# Raspberry_Pi.net
KiCad netlist of a schematic drawn in EAGLE
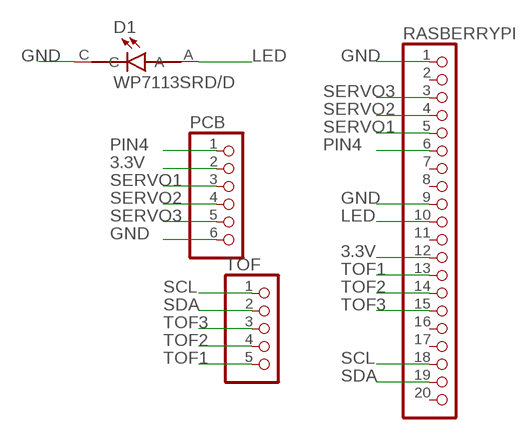
[diagram p0: schematic, sheet 1]

(export (version "E")
  (design (tool "Eeschema 10.0.6"))
  (components
    (comp (ref "D1")
      (value "WP7113SRD/D")
      (footprint "eagle-import:LED_WP7113SRD_D")
      (fields (field (name "MF") "Kingbright"))
      (libsource (lib "eagle-import") (part "WP7113SRD/D"))
    )
    (comp (ref "PCB")
      (value "PINHD-1X6")
      (footprint "eagle-import:1X06")
      (libsource (lib "eagle-import") (part "PINHD-1X6"))
    )
    (comp (ref "RASBERRYPI")
      (value "PINHD-1X20")
      (footprint "eagle-import:1X20")
      (libsource (lib "eagle-import") (part "PINHD-1X20"))
    )
    (comp (ref "TOF")
      (value "PINHD-1X5")
      (footprint "eagle-import:1X05")
      (libsource (lib "eagle-import") (part "PINHD-1X5"))
    )
  )
  (nets
    (net (code "1") (name "/3.3V") (class "Default")
      (node (ref "PCB") (pin "2") (pinfunction "2_2") (pintype "passive"))
      (node (ref "RASBERRYPI") (pin "12") (pinfunction "12_12") (pintype "passive"))
    )
    (net (code "2") (name "/GND") (class "Default")
      (node (ref "D1") (pin "C") (pinfunction "C_C") (pintype "passive"))
      (node (ref "PCB") (pin "6") (pinfunction "6_6") (pintype "passive"))
      (node (ref "RASBERRYPI") (pin "1") (pinfunction "1_1") (pintype "passive"))
      (node (ref "RASBERRYPI") (pin "9") (pinfunction "9_9") (pintype "passive"))
    )
    (net (code "3") (name "/LED") (class "Default")
      (node (ref "D1") (pin "A") (pinfunction "A_A") (pintype "passive"))
      (node (ref "RASBERRYPI") (pin "10") (pinfunction "10_10") (pintype "passive"))
    )
    (net (code "4") (name "/PIN4") (class "Default")
      (node (ref "PCB") (pin "1") (pinfunction "1_1") (pintype "passive"))
      (node (ref "RASBERRYPI") (pin "6") (pinfunction "6_6") (pintype "passive"))
    )
    (net (code "5") (name "/SCL") (class "Default")
      (node (ref "RASBERRYPI") (pin "18") (pinfunction "18_18") (pintype "passive"))
      (node (ref "TOF") (pin "1") (pinfunction "1_1") (pintype "passive"))
    )
    (net (code "6") (name "/SDA") (class "Default")
      (node (ref "RASBERRYPI") (pin "19") (pinfunction "19_19") (pintype "passive"))
      (node (ref "TOF") (pin "2") (pinfunction "2_2") (pintype "passive"))
    )
    (net (code "7") (name "/SERVO1") (class "Default")
      (node (ref "PCB") (pin "3") (pinfunction "3_3") (pintype "passive"))
      (node (ref "RASBERRYPI") (pin "5") (pinfunction "5_5") (pintype "passive"))
    )
    (net (code "8") (name "/SERVO2") (class "Default")
      (node (ref "PCB") (pin "4") (pinfunction "4_4") (pintype "passive"))
      (node (ref "RASBERRYPI") (pin "4") (pinfunction "4_4") (pintype "passive"))
    )
    (net (code "9") (name "/SERVO3") (class "Default")
      (node (ref "PCB") (pin "5") (pinfunction "5_5") (pintype "passive"))
      (node (ref "RASBERRYPI") (pin "3") (pinfunction "3_3") (pintype "passive"))
    )
    (net (code "10") (name "/TOF1") (class "Default")
      (node (ref "RASBERRYPI") (pin "13") (pinfunction "13_13") (pintype "passive"))
      (node (ref "TOF") (pin "5") (pinfunction "5_5") (pintype "passive"))
    )
    (net (code "11") (name "/TOF2") (class "Default")
      (node (ref "RASBERRYPI") (pin "14") (pinfunction "14_14") (pintype "passive"))
      (node (ref "TOF") (pin "4") (pinfunction "4_4") (pintype "passive"))
    )
    (net (code "12") (name "/TOF3") (class "Default")
      (node (ref "RASBERRYPI") (pin "15") (pinfunction "15_15") (pintype "passive"))
      (node (ref "TOF") (pin "3") (pinfunction "3_3") (pintype "passive"))
    )
    (net (code "13") (name "unconnected-(RASBERRYPI-Pad2)") (class "Default")
      (node (ref "RASBERRYPI") (pin "2") (pinfunction "2_2") (pintype "passive"))
    )
    (net (code "14") (name "unconnected-(RASBERRYPI-Pad7)") (class "Default")
      (node (ref "RASBERRYPI") (pin "7") (pinfunction "7_7") (pintype "passive"))
    )
    (net (code "15") (name "unconnected-(RASBERRYPI-Pad8)") (class "Default")
      (node (ref "RASBERRYPI") (pin "8") (pinfunction "8_8") (pintype "passive"))
    )
    (net (code "16") (name "unconnected-(RASBERRYPI-Pad11)") (class "Default")
      (node (ref "RASBERRYPI") (pin "11") (pinfunction "11_11") (pintype "passive"))
    )
    (net (code "17") (name "unconnected-(RASBERRYPI-Pad16)") (class "Default")
      (node (ref "RASBERRYPI") (pin "16") (pinfunction "16_16") (pintype "passive"))
    )
    (net (code "18") (name "unconnected-(RASBERRYPI-Pad17)") (class "Default")
      (node (ref "RASBERRYPI") (pin "17") (pinfunction "17_17") (pintype "passive"))
    )
    (net (code "19") (name "unconnected-(RASBERRYPI-Pad20)") (class "Default")
      (node (ref "RASBERRYPI") (pin "20") (pinfunction "20_20") (pintype "passive"))
    )
  )
)
